# 09_servo.net
KiCad netlist of a schematic drawn in Altium Designer
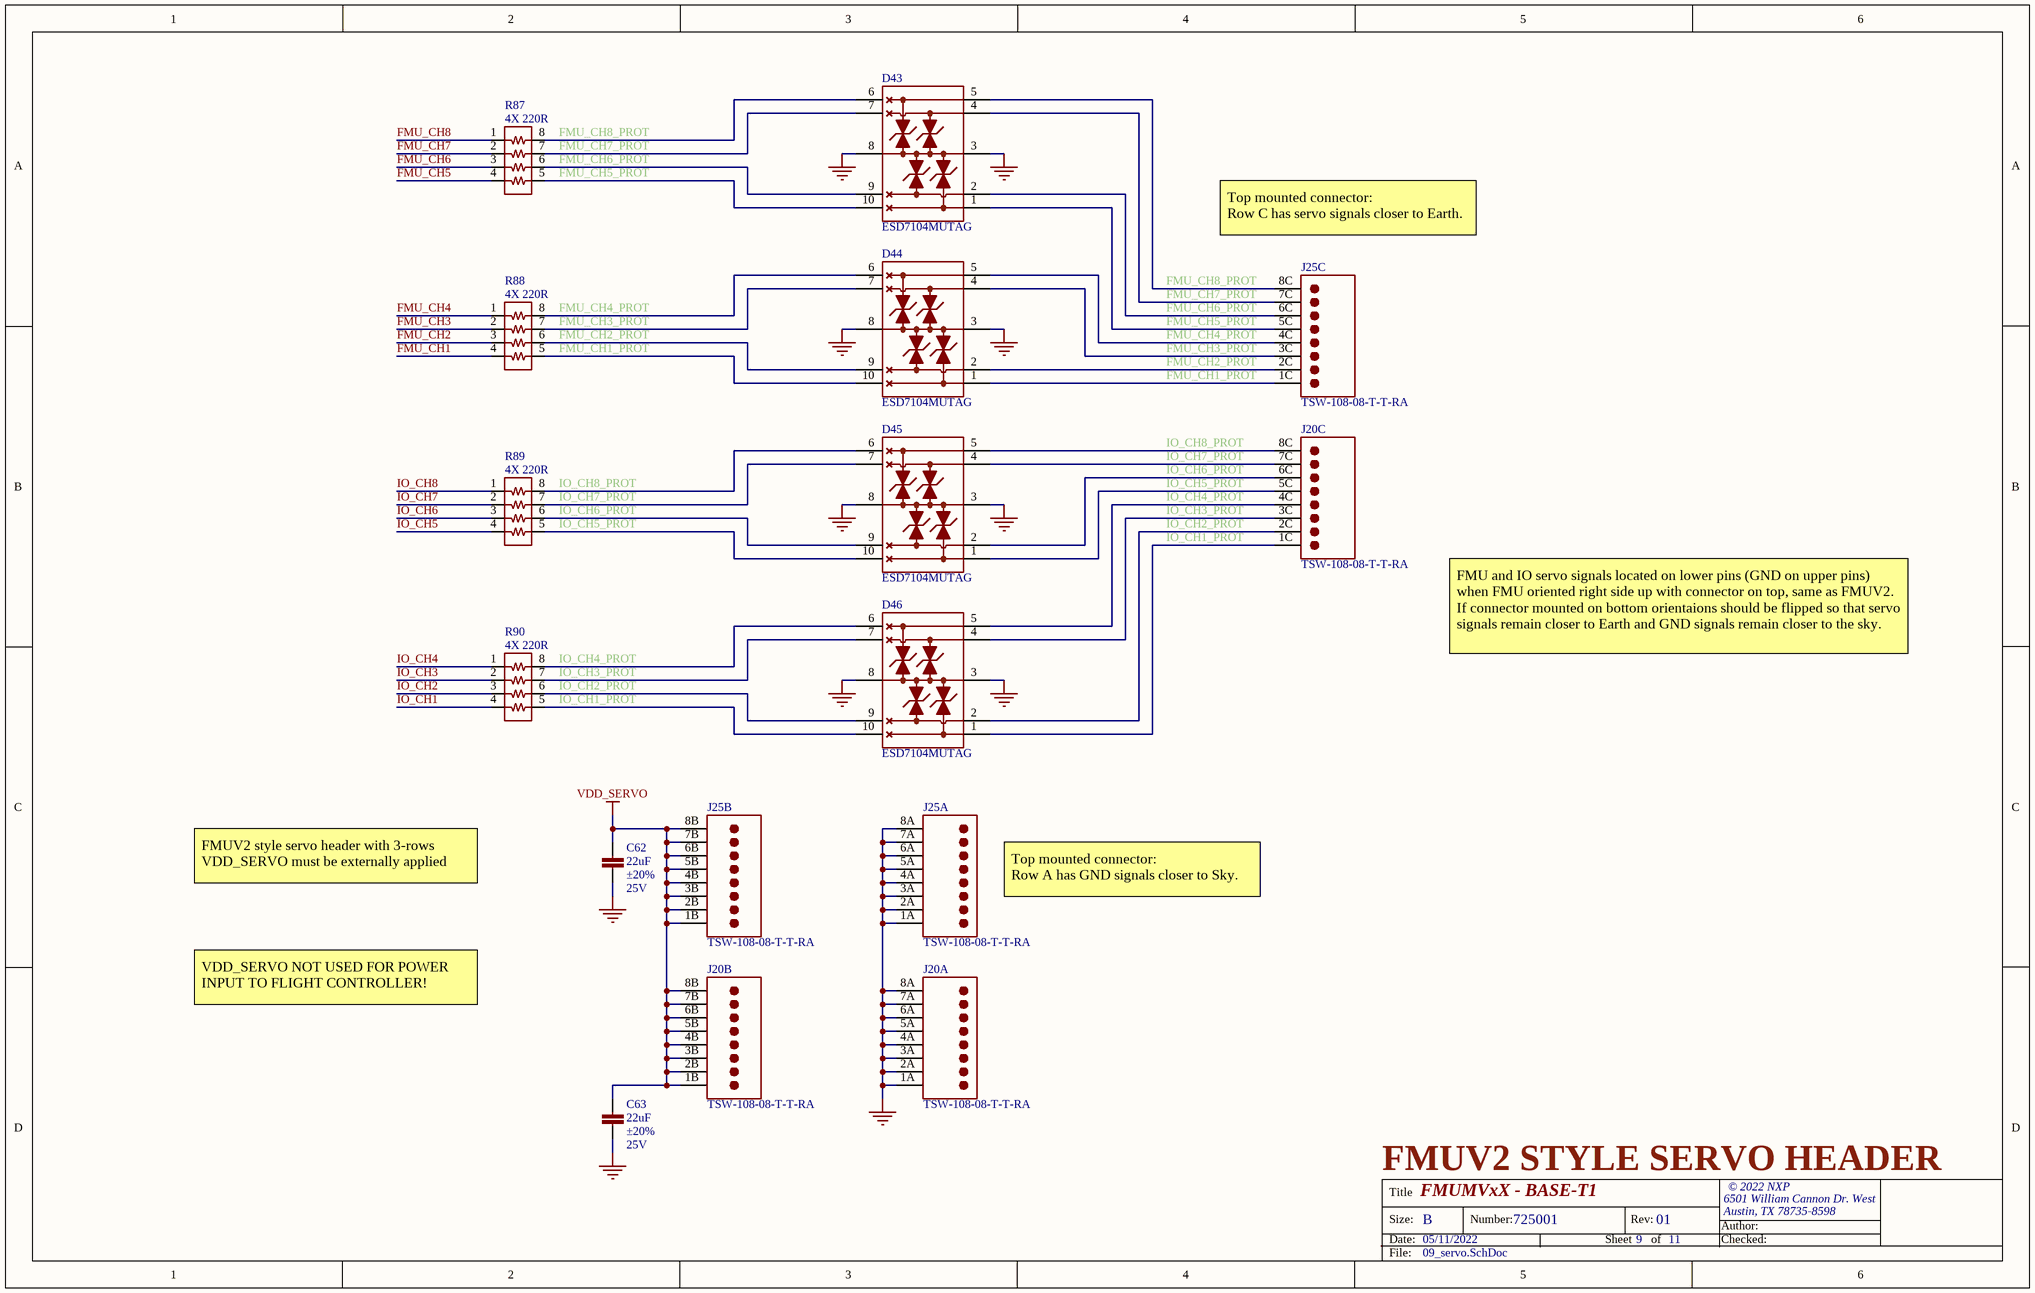
[diagram p0: 09_servo.SchDoc]

(export (version "E")
  (design (tool "Eeschema 10.0.6"))
  (components
    (comp (ref "C62")
      (value "22uF")
      (footprint "CAPC200X125X70L40N")
      (description "CAP CER 22UF 20% 25V X5R 0805")
      (fields
        (field (name "MANUFACTURER") "Murata Electronics")
        (field (name "MANUFACTURER PART NUMBER") "GRT21BR61E226ME13L")
        (field (name "TOLERANCE") "±20%")
        (field (name "VOLTAGE - RATED") "25V")
      )
      (libsource (lib "NscDG_Integrated_Library") (part "CAP_22UF_20%_25V_X5R_0805"))
    )
    (comp (ref "C63")
      (value "22uF")
      (footprint "CAPC200X125X70L40N")
      (description "CAP CER 22UF 20% 25V X5R 0805")
      (fields
        (field (name "MANUFACTURER") "Murata Electronics")
        (field (name "MANUFACTURER PART NUMBER") "GRT21BR61E226ME13L")
        (field (name "TOLERANCE") "±20%")
        (field (name "VOLTAGE - RATED") "25V")
      )
      (libsource (lib "NscDG_Integrated_Library") (part "CAP_22UF_20%_25V_X5R_0805"))
    )
    (comp (ref "D43")
      (value "DIODE TVS BIDIRECTIONAL 5V 10V 10UDFN")
      (footprint "UDFN10P50_250X100X55L35X20N")
      (fields
        (field (name "MANUFACTURER") "ON Semiconductor")
        (field (name "MANUFACTURER PART NUMBER") "ESD7104MUTAG")
      )
      (libsource (lib "NscDG_Integrated_Library") (part "DIODE_TVS_4X_10UDFN"))
    )
    (comp (ref "D44")
      (value "DIODE TVS BIDIRECTIONAL 5V 10V 10UDFN")
      (footprint "UDFN10P50_250X100X55L35X20N")
      (fields
        (field (name "MANUFACTURER") "ON Semiconductor")
        (field (name "MANUFACTURER PART NUMBER") "ESD7104MUTAG")
      )
      (libsource (lib "NscDG_Integrated_Library") (part "DIODE_TVS_4X_10UDFN"))
    )
    (comp (ref "D45")
      (value "DIODE TVS BIDIRECTIONAL 5V 10V 10UDFN")
      (footprint "UDFN10P50_250X100X55L35X20N")
      (fields
        (field (name "MANUFACTURER") "ON Semiconductor")
        (field (name "MANUFACTURER PART NUMBER") "ESD7104MUTAG")
      )
      (libsource (lib "NscDG_Integrated_Library") (part "DIODE_TVS_4X_10UDFN"))
    )
    (comp (ref "D46")
      (value "DIODE TVS BIDIRECTIONAL 5V 10V 10UDFN")
      (footprint "UDFN10P50_250X100X55L35X20N")
      (fields
        (field (name "MANUFACTURER") "ON Semiconductor")
        (field (name "MANUFACTURER PART NUMBER") "ESD7104MUTAG")
      )
      (libsource (lib "NscDG_Integrated_Library") (part "DIODE_TVS_4X_10UDFN"))
    )
    (comp (ref "J20")
      (value "CONN HDR 24POS 2.54MM RA TH")
      (footprint "3X8RA_ABC")
      (fields
        (field (name "MANUFACTURER") "Samtec")
        (field (name "MANUFACTURER PART NUMBER") "TSW-108-08-T-T-RA")
      )
      (libsource (lib "NscDG_Integrated_Library") (part "CONN_HDR_3X8RA_TH"))
    )
    (comp (ref "J25")
      (value "CONN HDR 24POS 2.54MM RA TH")
      (footprint "3X8RA_ABC")
      (fields
        (field (name "MANUFACTURER") "Samtec")
        (field (name "MANUFACTURER PART NUMBER") "TSW-108-08-T-T-RA")
      )
      (libsource (lib "NscDG_Integrated_Library") (part "CONN_HDR_3X8RA_TH"))
    )
    (comp (ref "R87")
      (value "4X 220R")
      (footprint "RESCAF8P80_320X160X61L30X65N")
      (description "RES ARRAY 4 RES 220 OHM 1206")
      (fields (field (name "TOLERANCE") "±5%") (field (name "MANUFACTURER") "Yageo"))
      (libsource (lib "NscDG_Integrated_Library") (part "RES_ARRAY_220_5%_1/16W_1206"))
    )
    (comp (ref "R88")
      (value "4X 220R")
      (footprint "RESCAF8P80_320X160X61L30X65N")
      (description "RES ARRAY 4 RES 220 OHM 1206")
      (fields (field (name "TOLERANCE") "±5%") (field (name "MANUFACTURER") "Yageo"))
      (libsource (lib "NscDG_Integrated_Library") (part "RES_ARRAY_220_5%_1/16W_1206"))
    )
    (comp (ref "R89")
      (value "4X 220R")
      (footprint "RESCAF8P80_320X160X61L30X65N")
      (description "RES ARRAY 4 RES 220 OHM 1206")
      (fields (field (name "TOLERANCE") "±5%") (field (name "MANUFACTURER") "Yageo"))
      (libsource (lib "NscDG_Integrated_Library") (part "RES_ARRAY_220_5%_1/16W_1206"))
    )
    (comp (ref "R90")
      (value "4X 220R")
      (footprint "RESCAF8P80_320X160X61L30X65N")
      (description "RES ARRAY 4 RES 220 OHM 1206")
      (fields (field (name "TOLERANCE") "±5%") (field (name "MANUFACTURER") "Yageo"))
      (libsource (lib "NscDG_Integrated_Library") (part "RES_ARRAY_220_5%_1/16W_1206"))
    )
  )
  (nets
    (net (code "1") (name "/FMU_CH1") (class "Default")
      (node (ref "R88") (pin "4") (pinfunction "4_4") (pintype "passive"))
    )
    (net (code "2") (name "/FMU_CH1_PROT") (class "Default")
      (node (ref "D44") (pin "1") (pinfunction "1_1") (pintype "passive"))
      (node (ref "D44") (pin "10") (pinfunction "NC_10") (pintype "passive"))
      (node (ref "J25") (pin "1C") (pinfunction "1C_1C") (pintype "passive"))
      (node (ref "R88") (pin "5") (pinfunction "5_5") (pintype "passive"))
    )
    (net (code "3") (name "/FMU_CH2") (class "Default")
      (node (ref "R88") (pin "3") (pinfunction "3_3") (pintype "passive"))
    )
    (net (code "4") (name "/FMU_CH2_PROT") (class "Default")
      (node (ref "D44") (pin "2") (pinfunction "2_2") (pintype "passive"))
      (node (ref "D44") (pin "9") (pinfunction "NC_9") (pintype "passive"))
      (node (ref "J25") (pin "2C") (pinfunction "2C_2C") (pintype "passive"))
      (node (ref "R88") (pin "6") (pinfunction "6_6") (pintype "passive"))
    )
    (net (code "5") (name "/FMU_CH3") (class "Default")
      (node (ref "R88") (pin "2") (pinfunction "2_2") (pintype "passive"))
    )
    (net (code "6") (name "/FMU_CH3_PROT") (class "Default")
      (node (ref "D44") (pin "4") (pinfunction "4_4") (pintype "passive"))
      (node (ref "D44") (pin "7") (pinfunction "NC_7") (pintype "passive"))
      (node (ref "J25") (pin "3C") (pinfunction "3C_3C") (pintype "passive"))
      (node (ref "R88") (pin "7") (pinfunction "7_7") (pintype "passive"))
    )
    (net (code "7") (name "/FMU_CH4") (class "Default")
      (node (ref "R88") (pin "1") (pinfunction "1_1") (pintype "passive"))
    )
    (net (code "8") (name "/FMU_CH4_PROT") (class "Default")
      (node (ref "D44") (pin "5") (pinfunction "5_5") (pintype "passive"))
      (node (ref "D44") (pin "6") (pinfunction "NC_6") (pintype "passive"))
      (node (ref "J25") (pin "4C") (pinfunction "4C_4C") (pintype "passive"))
      (node (ref "R88") (pin "8") (pinfunction "8_8") (pintype "passive"))
    )
    (net (code "9") (name "/FMU_CH5") (class "Default")
      (node (ref "R87") (pin "4") (pinfunction "4_4") (pintype "passive"))
    )
    (net (code "10") (name "/FMU_CH5_PROT") (class "Default")
      (node (ref "D43") (pin "1") (pinfunction "1_1") (pintype "passive"))
      (node (ref "D43") (pin "10") (pinfunction "NC_10") (pintype "passive"))
      (node (ref "J25") (pin "5C") (pinfunction "5C_5C") (pintype "passive"))
      (node (ref "R87") (pin "5") (pinfunction "5_5") (pintype "passive"))
    )
    (net (code "11") (name "/FMU_CH6") (class "Default")
      (node (ref "R87") (pin "3") (pinfunction "3_3") (pintype "passive"))
    )
    (net (code "12") (name "/FMU_CH6_PROT") (class "Default")
      (node (ref "D43") (pin "2") (pinfunction "2_2") (pintype "passive"))
      (node (ref "D43") (pin "9") (pinfunction "NC_9") (pintype "passive"))
      (node (ref "J25") (pin "6C") (pinfunction "6C_6C") (pintype "passive"))
      (node (ref "R87") (pin "6") (pinfunction "6_6") (pintype "passive"))
    )
    (net (code "13") (name "/FMU_CH7") (class "Default")
      (node (ref "R87") (pin "2") (pinfunction "2_2") (pintype "passive"))
    )
    (net (code "14") (name "/FMU_CH7_PROT") (class "Default")
      (node (ref "D43") (pin "4") (pinfunction "4_4") (pintype "passive"))
      (node (ref "D43") (pin "7") (pinfunction "NC_7") (pintype "passive"))
      (node (ref "J25") (pin "7C") (pinfunction "7C_7C") (pintype "passive"))
      (node (ref "R87") (pin "7") (pinfunction "7_7") (pintype "passive"))
    )
    (net (code "15") (name "/FMU_CH8") (class "Default")
      (node (ref "R87") (pin "1") (pinfunction "1_1") (pintype "passive"))
    )
    (net (code "16") (name "/FMU_CH8_PROT") (class "Default")
      (node (ref "D43") (pin "5") (pinfunction "5_5") (pintype "passive"))
      (node (ref "D43") (pin "6") (pinfunction "NC_6") (pintype "passive"))
      (node (ref "J25") (pin "8C") (pinfunction "8C_8C") (pintype "passive"))
      (node (ref "R87") (pin "8") (pinfunction "8_8") (pintype "passive"))
    )
    (net (code "17") (name "/IO_CH1") (class "Default")
      (node (ref "R90") (pin "4") (pinfunction "4_4") (pintype "passive"))
    )
    (net (code "18") (name "/IO_CH1_PROT") (class "Default")
      (node (ref "D46") (pin "1") (pinfunction "1_1") (pintype "passive"))
      (node (ref "D46") (pin "10") (pinfunction "NC_10") (pintype "passive"))
      (node (ref "J20") (pin "1C") (pinfunction "1C_1C") (pintype "passive"))
      (node (ref "R90") (pin "5") (pinfunction "5_5") (pintype "passive"))
    )
    (net (code "19") (name "/IO_CH2") (class "Default")
      (node (ref "R90") (pin "3") (pinfunction "3_3") (pintype "passive"))
    )
    (net (code "20") (name "/IO_CH2_PROT") (class "Default")
      (node (ref "D46") (pin "2") (pinfunction "2_2") (pintype "passive"))
      (node (ref "D46") (pin "9") (pinfunction "NC_9") (pintype "passive"))
      (node (ref "J20") (pin "2C") (pinfunction "2C_2C") (pintype "passive"))
      (node (ref "R90") (pin "6") (pinfunction "6_6") (pintype "passive"))
    )
    (net (code "21") (name "/IO_CH3") (class "Default")
      (node (ref "R90") (pin "2") (pinfunction "2_2") (pintype "passive"))
    )
    (net (code "22") (name "/IO_CH3_PROT") (class "Default")
      (node (ref "D46") (pin "4") (pinfunction "4_4") (pintype "passive"))
      (node (ref "D46") (pin "7") (pinfunction "NC_7") (pintype "passive"))
      (node (ref "J20") (pin "3C") (pinfunction "3C_3C") (pintype "passive"))
      (node (ref "R90") (pin "7") (pinfunction "7_7") (pintype "passive"))
    )
    (net (code "23") (name "/IO_CH4") (class "Default")
      (node (ref "R90") (pin "1") (pinfunction "1_1") (pintype "passive"))
    )
    (net (code "24") (name "/IO_CH4_PROT") (class "Default")
      (node (ref "D46") (pin "5") (pinfunction "5_5") (pintype "passive"))
      (node (ref "D46") (pin "6") (pinfunction "NC_6") (pintype "passive"))
      (node (ref "J20") (pin "4C") (pinfunction "4C_4C") (pintype "passive"))
      (node (ref "R90") (pin "8") (pinfunction "8_8") (pintype "passive"))
    )
    (net (code "25") (name "/IO_CH5") (class "Default")
      (node (ref "R89") (pin "4") (pinfunction "4_4") (pintype "passive"))
    )
    (net (code "26") (name "/IO_CH5_PROT") (class "Default")
      (node (ref "D45") (pin "1") (pinfunction "1_1") (pintype "passive"))
      (node (ref "D45") (pin "10") (pinfunction "NC_10") (pintype "passive"))
      (node (ref "J20") (pin "5C") (pinfunction "5C_5C") (pintype "passive"))
      (node (ref "R89") (pin "5") (pinfunction "5_5") (pintype "passive"))
    )
    (net (code "27") (name "/IO_CH6") (class "Default")
      (node (ref "R89") (pin "3") (pinfunction "3_3") (pintype "passive"))
    )
    (net (code "28") (name "/IO_CH6_PROT") (class "Default")
      (node (ref "D45") (pin "2") (pinfunction "2_2") (pintype "passive"))
      (node (ref "D45") (pin "9") (pinfunction "NC_9") (pintype "passive"))
      (node (ref "J20") (pin "6C") (pinfunction "6C_6C") (pintype "passive"))
      (node (ref "R89") (pin "6") (pinfunction "6_6") (pintype "passive"))
    )
    (net (code "29") (name "/IO_CH7") (class "Default")
      (node (ref "R89") (pin "2") (pinfunction "2_2") (pintype "passive"))
    )
    (net (code "30") (name "/IO_CH7_PROT") (class "Default")
      (node (ref "D45") (pin "4") (pinfunction "4_4") (pintype "passive"))
      (node (ref "D45") (pin "7") (pinfunction "NC_7") (pintype "passive"))
      (node (ref "J20") (pin "7C") (pinfunction "7C_7C") (pintype "passive"))
      (node (ref "R89") (pin "7") (pinfunction "7_7") (pintype "passive"))
    )
    (net (code "31") (name "/IO_CH8") (class "Default")
      (node (ref "R89") (pin "1") (pinfunction "1_1") (pintype "passive"))
    )
    (net (code "32") (name "/IO_CH8_PROT") (class "Default")
      (node (ref "D45") (pin "5") (pinfunction "5_5") (pintype "passive"))
      (node (ref "D45") (pin "6") (pinfunction "NC_6") (pintype "passive"))
      (node (ref "J20") (pin "8C") (pinfunction "8C_8C") (pintype "passive"))
      (node (ref "R89") (pin "8") (pinfunction "8_8") (pintype "passive"))
    )
    (net (code "33") (name "GND") (class "Default")
      (node (ref "C62") (pin "2") (pinfunction "2_2") (pintype "passive"))
      (node (ref "C63") (pin "2") (pinfunction "2_2") (pintype "passive"))
      (node (ref "D43") (pin "3") (pinfunction "GND_3") (pintype "passive"))
      (node (ref "D43") (pin "8") (pinfunction "GND_8") (pintype "passive"))
      (node (ref "D44") (pin "3") (pinfunction "GND_3") (pintype "passive"))
      (node (ref "D44") (pin "8") (pinfunction "GND_8") (pintype "passive"))
      (node (ref "D45") (pin "3") (pinfunction "GND_3") (pintype "passive"))
      (node (ref "D45") (pin "8") (pinfunction "GND_8") (pintype "passive"))
      (node (ref "D46") (pin "3") (pinfunction "GND_3") (pintype "passive"))
      (node (ref "D46") (pin "8") (pinfunction "GND_8") (pintype "passive"))
      (node (ref "J20") (pin "1A") (pinfunction "1A_1A") (pintype "passive"))
      (node (ref "J20") (pin "2A") (pinfunction "2A_2A") (pintype "passive"))
      (node (ref "J20") (pin "3A") (pinfunction "3A_3A") (pintype "passive"))
      (node (ref "J20") (pin "4A") (pinfunction "4A_4A") (pintype "passive"))
      (node (ref "J20") (pin "5A") (pinfunction "5A_5A") (pintype "passive"))
      (node (ref "J20") (pin "6A") (pinfunction "6A_6A") (pintype "passive"))
      (node (ref "J20") (pin "7A") (pinfunction "7A_7A") (pintype "passive"))
      (node (ref "J20") (pin "8A") (pinfunction "8A_8A") (pintype "passive"))
      (node (ref "J25") (pin "1A") (pinfunction "1A_1A") (pintype "passive"))
      (node (ref "J25") (pin "2A") (pinfunction "2A_2A") (pintype "passive"))
      (node (ref "J25") (pin "3A") (pinfunction "3A_3A") (pintype "passive"))
      (node (ref "J25") (pin "4A") (pinfunction "4A_4A") (pintype "passive"))
      (node (ref "J25") (pin "5A") (pinfunction "5A_5A") (pintype "passive"))
      (node (ref "J25") (pin "6A") (pinfunction "6A_6A") (pintype "passive"))
      (node (ref "J25") (pin "7A") (pinfunction "7A_7A") (pintype "passive"))
      (node (ref "J25") (pin "8A") (pinfunction "8A_8A") (pintype "passive"))
    )
    (net (code "34") (name "VDD_SERVO") (class "Default")
      (node (ref "C62") (pin "1") (pinfunction "1_1") (pintype "passive"))
      (node (ref "C63") (pin "1") (pinfunction "1_1") (pintype "passive"))
      (node (ref "J20") (pin "1B") (pinfunction "1B_1B") (pintype "passive"))
      (node (ref "J20") (pin "2B") (pinfunction "2B_2B") (pintype "passive"))
      (node (ref "J20") (pin "3B") (pinfunction "3B_3B") (pintype "passive"))
      (node (ref "J20") (pin "4B") (pinfunction "4B_4B") (pintype "passive"))
      (node (ref "J20") (pin "5B") (pinfunction "5B_5B") (pintype "passive"))
      (node (ref "J20") (pin "6B") (pinfunction "6B_6B") (pintype "passive"))
      (node (ref "J20") (pin "7B") (pinfunction "7B_7B") (pintype "passive"))
      (node (ref "J20") (pin "8B") (pinfunction "8B_8B") (pintype "passive"))
      (node (ref "J25") (pin "1B") (pinfunction "1B_1B") (pintype "passive"))
      (node (ref "J25") (pin "2B") (pinfunction "2B_2B") (pintype "passive"))
      (node (ref "J25") (pin "3B") (pinfunction "3B_3B") (pintype "passive"))
      (node (ref "J25") (pin "4B") (pinfunction "4B_4B") (pintype "passive"))
      (node (ref "J25") (pin "5B") (pinfunction "5B_5B") (pintype "passive"))
      (node (ref "J25") (pin "6B") (pinfunction "6B_6B") (pintype "passive"))
      (node (ref "J25") (pin "7B") (pinfunction "7B_7B") (pintype "passive"))
      (node (ref "J25") (pin "8B") (pinfunction "8B_8B") (pintype "passive"))
    )
  )
)
